# carte_imprimante.net
KiCad netlist of a schematic drawn in EAGLE
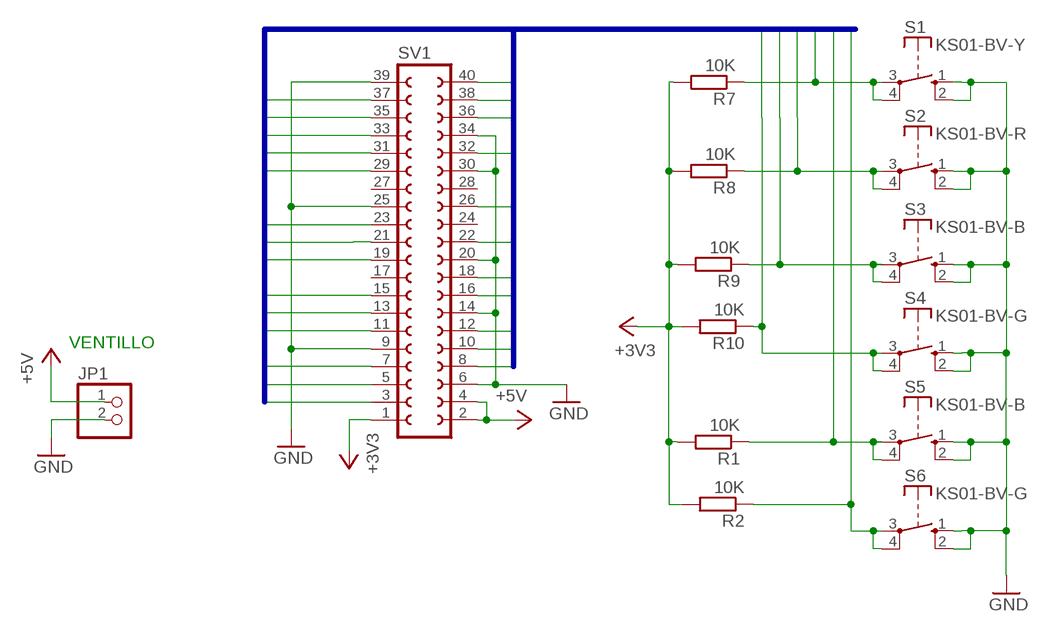
[diagram p0: schematic, sheet 1]

(export (version "E")
  (design (tool "Eeschema 10.0.6"))
  (components
    (comp (ref "JP1")
      (value "PINHD-1X02_2.54-S")
      (footprint "eagle-import:1X02-S")
      (libsource (lib "eagle-import") (part "PINHD-1X02_2.54-S"))
    )
    (comp (ref "R1")
      (value "10K")
      (footprint "eagle-import:R0603")
      (libsource (lib "eagle-import") (part "R-EU_R0603"))
    )
    (comp (ref "R2")
      (value "10K")
      (footprint "eagle-import:R0603")
      (libsource (lib "eagle-import") (part "R-EU_R0603"))
    )
    (comp (ref "R7")
      (value "10K")
      (footprint "eagle-import:R0603")
      (libsource (lib "eagle-import") (part "R-EU_R0603"))
    )
    (comp (ref "R8")
      (value "10K")
      (footprint "eagle-import:R0603")
      (libsource (lib "eagle-import") (part "R-EU_R0603"))
    )
    (comp (ref "R9")
      (value "10K")
      (footprint "eagle-import:R0603")
      (libsource (lib "eagle-import") (part "R-EU_R0603"))
    )
    (comp (ref "R10")
      (value "10K")
      (footprint "eagle-import:R0603")
      (libsource (lib "eagle-import") (part "R-EU_R0603"))
    )
    (comp (ref "S1")
      (value "KS01-BV-Y")
      (footprint "eagle-import:DT6")
      (libsource (lib "eagle-import") (part "DT6"))
    )
    (comp (ref "S2")
      (value "KS01-BV-R")
      (footprint "eagle-import:DT6")
      (libsource (lib "eagle-import") (part "DT6"))
    )
    (comp (ref "S3")
      (value "KS01-BV-B")
      (footprint "eagle-import:DT6")
      (libsource (lib "eagle-import") (part "DT6"))
    )
    (comp (ref "S4")
      (value "KS01-BV-G")
      (footprint "eagle-import:DT6")
      (libsource (lib "eagle-import") (part "DT6"))
    )
    (comp (ref "S5")
      (value "KS01-BV-B")
      (footprint "eagle-import:DT6")
      (libsource (lib "eagle-import") (part "DT6"))
    )
    (comp (ref "S6")
      (value "KS01-BV-G")
      (footprint "eagle-import:DT6")
      (libsource (lib "eagle-import") (part "DT6"))
    )
    (comp (ref "SV1")
      (value "FE20-2")
      (footprint "eagle-import:FE20-2")
      (libsource (lib "eagle-import") (part "FE20-2"))
    )
  )
  (nets
    (net (code "1") (name "+3V3") (class "Default")
      (node (ref "R1") (pin "2") (pinfunction "2_2") (pintype "passive"))
      (node (ref "R10") (pin "2") (pinfunction "2_2") (pintype "passive"))
      (node (ref "R2") (pin "2") (pinfunction "2_2") (pintype "passive"))
      (node (ref "R7") (pin "2") (pinfunction "2_2") (pintype "passive"))
      (node (ref "R8") (pin "2") (pinfunction "2_2") (pintype "passive"))
      (node (ref "R9") (pin "2") (pinfunction "2_2") (pintype "passive"))
      (node (ref "SV1") (pin "1") (pinfunction "1_1") (pintype "passive"))
    )
    (net (code "2") (name "+5V") (class "Default")
      (node (ref "JP1") (pin "1") (pinfunction "1_1") (pintype "passive"))
      (node (ref "SV1") (pin "2") (pinfunction "2_2") (pintype "passive"))
      (node (ref "SV1") (pin "4") (pinfunction "4_4") (pintype "passive"))
    )
    (net (code "3") (name "/GPIO10*") (class "Default")
      (node (ref "R7") (pin "1") (pinfunction "1_1") (pintype "passive"))
      (node (ref "S1") (pin "3") (pinfunction "P_3") (pintype "passive"))
      (node (ref "S1") (pin "4") (pinfunction "P_4") (pintype "passive"))
      (node (ref "SV1") (pin "19") (pinfunction "19_19") (pintype "passive"))
    )
    (net (code "4") (name "/GPIO17") (class "Default")
      (node (ref "R10") (pin "1") (pinfunction "1_1") (pintype "passive"))
      (node (ref "S4") (pin "3") (pinfunction "P_3") (pintype "passive"))
      (node (ref "S4") (pin "4") (pinfunction "P_4") (pintype "passive"))
      (node (ref "SV1") (pin "11") (pinfunction "11_11") (pintype "passive"))
    )
    (net (code "5") (name "/GPIO19") (class "Default")
      (node (ref "R1") (pin "1") (pinfunction "1_1") (pintype "passive"))
      (node (ref "S5") (pin "3") (pinfunction "P_3") (pintype "passive"))
      (node (ref "S5") (pin "4") (pinfunction "P_4") (pintype "passive"))
      (node (ref "SV1") (pin "35") (pinfunction "35_35") (pintype "passive"))
    )
    (net (code "6") (name "/GPIO22") (class "Default")
      (node (ref "R8") (pin "1") (pinfunction "1_1") (pintype "passive"))
      (node (ref "S2") (pin "3") (pinfunction "P_3") (pintype "passive"))
      (node (ref "S2") (pin "4") (pinfunction "P_4") (pintype "passive"))
      (node (ref "SV1") (pin "15") (pinfunction "15_15") (pintype "passive"))
    )
    (net (code "7") (name "/GPIO26") (class "Default")
      (node (ref "R2") (pin "1") (pinfunction "1_1") (pintype "passive"))
      (node (ref "S6") (pin "3") (pinfunction "P_3") (pintype "passive"))
      (node (ref "S6") (pin "4") (pinfunction "P_4") (pintype "passive"))
      (node (ref "SV1") (pin "37") (pinfunction "37_37") (pintype "passive"))
    )
    (net (code "8") (name "/GPIO27") (class "Default")
      (node (ref "R9") (pin "1") (pinfunction "1_1") (pintype "passive"))
      (node (ref "S3") (pin "3") (pinfunction "P_3") (pintype "passive"))
      (node (ref "S3") (pin "4") (pinfunction "P_4") (pintype "passive"))
      (node (ref "SV1") (pin "13") (pinfunction "13_13") (pintype "passive"))
    )
    (net (code "9") (name "GND") (class "Default")
      (node (ref "JP1") (pin "2") (pinfunction "2_2") (pintype "passive"))
      (node (ref "S1") (pin "1") (pinfunction "S_1") (pintype "passive"))
      (node (ref "S1") (pin "2") (pinfunction "S_2") (pintype "passive"))
      (node (ref "S2") (pin "1") (pinfunction "S_1") (pintype "passive"))
      (node (ref "S2") (pin "2") (pinfunction "S_2") (pintype "passive"))
      (node (ref "S3") (pin "1") (pinfunction "S_1") (pintype "passive"))
      (node (ref "S3") (pin "2") (pinfunction "S_2") (pintype "passive"))
      (node (ref "S4") (pin "1") (pinfunction "S_1") (pintype "passive"))
      (node (ref "S4") (pin "2") (pinfunction "S_2") (pintype "passive"))
      (node (ref "S5") (pin "1") (pinfunction "S_1") (pintype "passive"))
      (node (ref "S5") (pin "2") (pinfunction "S_2") (pintype "passive"))
      (node (ref "S6") (pin "1") (pinfunction "S_1") (pintype "passive"))
      (node (ref "S6") (pin "2") (pinfunction "S_2") (pintype "passive"))
      (node (ref "SV1") (pin "14") (pinfunction "14_14") (pintype "passive"))
      (node (ref "SV1") (pin "20") (pinfunction "20_20") (pintype "passive"))
      (node (ref "SV1") (pin "25") (pinfunction "25_25") (pintype "passive"))
      (node (ref "SV1") (pin "30") (pinfunction "30_30") (pintype "passive"))
      (node (ref "SV1") (pin "34") (pinfunction "34_34") (pintype "passive"))
      (node (ref "SV1") (pin "39") (pinfunction "39_39") (pintype "passive"))
      (node (ref "SV1") (pin "6") (pinfunction "6_6") (pintype "passive"))
      (node (ref "SV1") (pin "9") (pinfunction "9_9") (pintype "passive"))
    )
    (net (code "10") (name "unconnected-(SV1-Pad3)") (class "Default")
      (node (ref "SV1") (pin "3") (pinfunction "3_3") (pintype "passive"))
    )
    (net (code "11") (name "unconnected-(SV1-Pad5)") (class "Default")
      (node (ref "SV1") (pin "5") (pinfunction "5_5") (pintype "passive"))
    )
    (net (code "12") (name "unconnected-(SV1-Pad7)") (class "Default")
      (node (ref "SV1") (pin "7") (pinfunction "7_7") (pintype "passive"))
    )
    (net (code "13") (name "unconnected-(SV1-Pad8)") (class "Default")
      (node (ref "SV1") (pin "8") (pinfunction "8_8") (pintype "passive"))
    )
    (net (code "14") (name "unconnected-(SV1-Pad10)") (class "Default")
      (node (ref "SV1") (pin "10") (pinfunction "10_10") (pintype "passive"))
    )
    (net (code "15") (name "unconnected-(SV1-Pad12)") (class "Default")
      (node (ref "SV1") (pin "12") (pinfunction "12_12") (pintype "passive"))
    )
    (net (code "16") (name "unconnected-(SV1-Pad16)") (class "Default")
      (node (ref "SV1") (pin "16") (pinfunction "16_16") (pintype "passive"))
    )
    (net (code "17") (name "unconnected-(SV1-Pad17)") (class "Default")
      (node (ref "SV1") (pin "17") (pinfunction "17_17") (pintype "passive"))
    )
    (net (code "18") (name "unconnected-(SV1-Pad18)") (class "Default")
      (node (ref "SV1") (pin "18") (pinfunction "18_18") (pintype "passive"))
    )
    (net (code "19") (name "unconnected-(SV1-Pad21)") (class "Default")
      (node (ref "SV1") (pin "21") (pinfunction "21_21") (pintype "passive"))
    )
    (net (code "20") (name "unconnected-(SV1-Pad22)") (class "Default")
      (node (ref "SV1") (pin "22") (pinfunction "22_22") (pintype "passive"))
    )
    (net (code "21") (name "unconnected-(SV1-Pad23)") (class "Default")
      (node (ref "SV1") (pin "23") (pinfunction "23_23") (pintype "passive"))
    )
    (net (code "22") (name "unconnected-(SV1-Pad24)") (class "Default")
      (node (ref "SV1") (pin "24") (pinfunction "24_24") (pintype "passive"))
    )
    (net (code "23") (name "unconnected-(SV1-Pad26)") (class "Default")
      (node (ref "SV1") (pin "26") (pinfunction "26_26") (pintype "passive"))
    )
    (net (code "24") (name "unconnected-(SV1-Pad27)") (class "Default")
      (node (ref "SV1") (pin "27") (pinfunction "27_27") (pintype "passive"))
    )
    (net (code "25") (name "unconnected-(SV1-Pad28)") (class "Default")
      (node (ref "SV1") (pin "28") (pinfunction "28_28") (pintype "passive"))
    )
    (net (code "26") (name "unconnected-(SV1-Pad29)") (class "Default")
      (node (ref "SV1") (pin "29") (pinfunction "29_29") (pintype "passive"))
    )
    (net (code "27") (name "unconnected-(SV1-Pad31)") (class "Default")
      (node (ref "SV1") (pin "31") (pinfunction "31_31") (pintype "passive"))
    )
    (net (code "28") (name "unconnected-(SV1-Pad32)") (class "Default")
      (node (ref "SV1") (pin "32") (pinfunction "32_32") (pintype "passive"))
    )
    (net (code "29") (name "unconnected-(SV1-Pad33)") (class "Default")
      (node (ref "SV1") (pin "33") (pinfunction "33_33") (pintype "passive"))
    )
    (net (code "30") (name "unconnected-(SV1-Pad36)") (class "Default")
      (node (ref "SV1") (pin "36") (pinfunction "36_36") (pintype "passive"))
    )
    (net (code "31") (name "unconnected-(SV1-Pad38)") (class "Default")
      (node (ref "SV1") (pin "38") (pinfunction "38_38") (pintype "passive"))
    )
    (net (code "32") (name "unconnected-(SV1-Pad40)") (class "Default")
      (node (ref "SV1") (pin "40") (pinfunction "40_40") (pintype "passive"))
    )
  )
)
